# Ethernet_HPS_Interface.net
KiCad netlist of a schematic drawn in Altium Designer
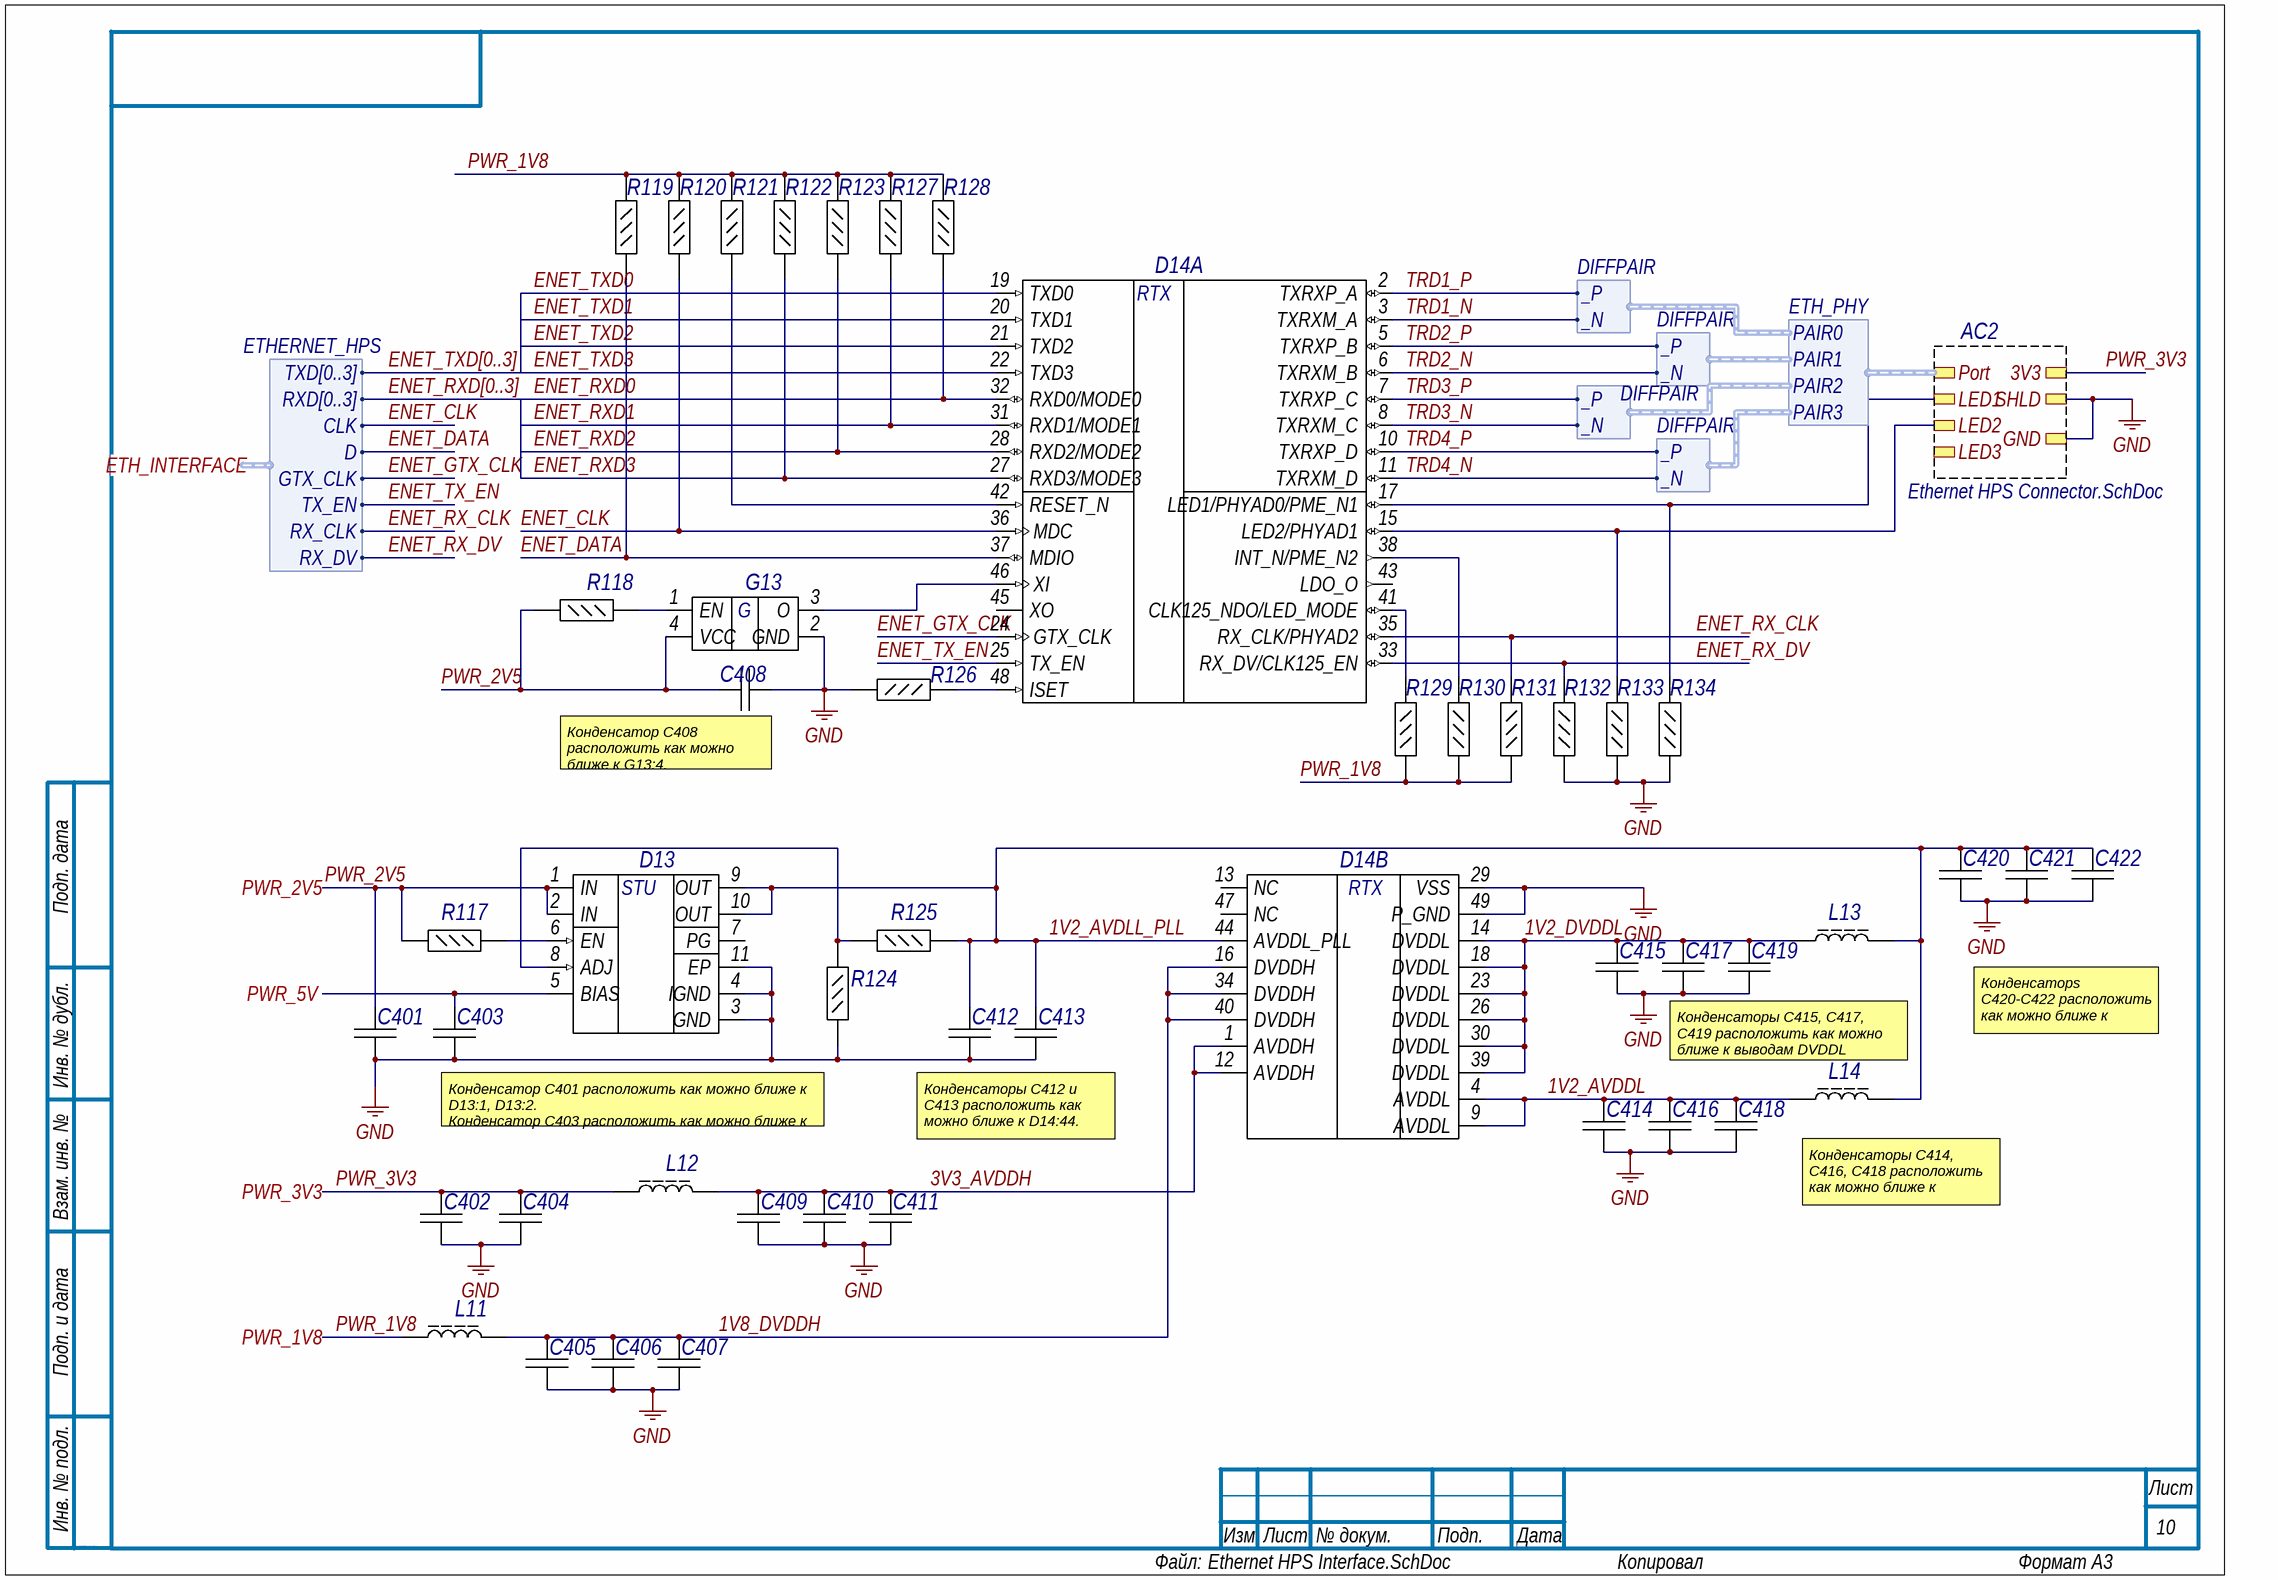
[diagram p0: Ethernet HPS Interface.SchDoc]

(export (version "E")
  (design (tool "Eeschema 10.0.6"))
  (components
    (comp (ref "C401")
      (value "C2012X5R1C106K085AC")
      (footprint "CAPC2013X100X20NL20")
      (description "Chip Capacitor, 10 uF, +/- 10%, 16 V, -55 to 85 degC, 0805 (2012 Metric), RoHS, Tape and Reel")
      (fields (field (name "TOLERANCE") "10%"))
      (libsource (lib "MiniPC DB") (part "CAP_NP"))
    )
    (comp (ref "C402")
      (value "C2012X5R1C106K085AC")
      (footprint "CAPC2013X100X20NL20")
      (description "Chip Capacitor, 10 uF, +/- 10%, 16 V, -55 to 85 degC, 0805 (2012 Metric), RoHS, Tape and Reel")
      (fields (field (name "TOLERANCE") "10%"))
      (libsource (lib "MiniPC DB") (part "CAP_NP"))
    )
    (comp (ref "C403")
      (value "CGB2A1X5R1E105K033BC")
      (footprint "CAPC1005X33X10LL5")
      (description "Chip Capacitor, 1 uF, +/- 10%, 25 V, -55 to 85 degC, 0402 (1005 Metric), RoHS, Tape and Reel")
      (fields (field (name "TOLERANCE") "10%"))
      (libsource (lib "MiniPC DB") (part "CAP_NP"))
    )
    (comp (ref "C404")
      (value "C2012X5R1C106K085AC")
      (footprint "CAPC2013X100X20NL20")
      (description "Chip Capacitor, 10 uF, +/- 10%, 16 V, -55 to 85 degC, 0805 (2012 Metric), RoHS, Tape and Reel")
      (fields (field (name "TOLERANCE") "10%"))
      (libsource (lib "MiniPC DB") (part "CAP_NP"))
    )
    (comp (ref "C405")
      (value "GRM31CR61E226KE15L")
      (footprint "CAPC3216X180X55ML20T25")
      (description "Chip Capacitor, 22 uF, +/- 10%, 25 V, -55 to 85 degC, 1206 (3216 Metric), RoHS, Tape and Reel")
      (fields (field (name "TOLERANCE") "10%"))
      (libsource (lib "MiniPC DB") (part "CAP_NP"))
    )
    (comp (ref "C406")
      (value "GRM188R61A225KE34x")
      (footprint "CAPC1608X90X35ML10T15")
      (description "Chip Capacitor, 2.2 uF, +/- 10%, 10 V, -55 to 85 degC, 0603 (1608 Metric), RoHS, Tape and Reel")
      (fields (field (name "TOLERANCE") "10%"))
      (libsource (lib "MiniPC DB") (part "CAP_NP"))
    )
    (comp (ref "C407")
      (value "C1005X7R1E104M")
      (footprint "CAPC1005X55X10LL05")
      (description "Chip Capacitor, 0.1 uF, +/- 20%, 25 V, -55 to 125 degC, 0402 (1005 Metric), RoHS, Tape and Reel")
      (fields (field (name "TOLERANCE") "20%"))
      (libsource (lib "MiniPC DB") (part "CAP_NP"))
    )
    (comp (ref "C408")
      (value "GRM155R71H103KA88D")
      (footprint "CAPC1005X55X25ML05T10")
      (description "Chip Capacitor, 10 nF, +/- 10%, 50 V, -55 to 125 degC, 0402 (1005 Metric), RoHS, Tape and Reel")
      (fields (field (name "TOLERANCE") "10%") (field (name "MANUFACTURER") "Basic Passives"))
      (libsource (lib "MiniPC DB") (part "CAP_NP"))
    )
    (comp (ref "C409")
      (value "GRM31CR61E226KE15L")
      (footprint "CAPC3216X180X55ML20T25")
      (description "Chip Capacitor, 22 uF, +/- 10%, 25 V, -55 to 85 degC, 1206 (3216 Metric), RoHS, Tape and Reel")
      (fields (field (name "TOLERANCE") "10%"))
      (libsource (lib "MiniPC DB") (part "CAP_NP"))
    )
    (comp (ref "C410")
      (value "GRM188R61A225KE34x")
      (footprint "CAPC1608X90X35ML10T15")
      (description "Chip Capacitor, 2.2 uF, +/- 10%, 10 V, -55 to 85 degC, 0603 (1608 Metric), RoHS, Tape and Reel")
      (fields (field (name "TOLERANCE") "10%"))
      (libsource (lib "MiniPC DB") (part "CAP_NP"))
    )
    (comp (ref "C411")
      (value "C1005X7R1E104M")
      (footprint "CAPC1005X55X10LL05")
      (description "Chip Capacitor, 0.1 uF, +/- 20%, 25 V, -55 to 125 degC, 0402 (1005 Metric), RoHS, Tape and Reel")
      (fields (field (name "TOLERANCE") "20%"))
      (libsource (lib "MiniPC DB") (part "CAP_NP"))
    )
    (comp (ref "C412")
      (value "GRM31CR61E226KE15L")
      (footprint "CAPC3216X180X55ML20T25")
      (description "Chip Capacitor, 22 uF, +/- 10%, 25 V, -55 to 85 degC, 1206 (3216 Metric), RoHS, Tape and Reel")
      (fields (field (name "TOLERANCE") "10%"))
      (libsource (lib "MiniPC DB") (part "CAP_NP"))
    )
    (comp (ref "C413")
      (value "GRM188R61A225KE34x")
      (footprint "CAPC1608X90X35ML10T15")
      (description "Chip Capacitor, 2.2 uF, +/- 10%, 10 V, -55 to 85 degC, 0603 (1608 Metric), RoHS, Tape and Reel")
      (fields (field (name "TOLERANCE") "10%"))
      (libsource (lib "MiniPC DB") (part "CAP_NP"))
    )
    (comp (ref "C414")
      (value "C1005X7R1E104M")
      (footprint "CAPC1005X55X10LL05")
      (description "Chip Capacitor, 0.1 uF, +/- 20%, 25 V, -55 to 125 degC, 0402 (1005 Metric), RoHS, Tape and Reel")
      (fields (field (name "TOLERANCE") "20%"))
      (libsource (lib "MiniPC DB") (part "CAP_NP"))
    )
    (comp (ref "C415")
      (value "C1005X7R1E104M")
      (footprint "CAPC1005X55X10LL05")
      (description "Chip Capacitor, 0.1 uF, +/- 20%, 25 V, -55 to 125 degC, 0402 (1005 Metric), RoHS, Tape and Reel")
      (fields (field (name "TOLERANCE") "20%"))
      (libsource (lib "MiniPC DB") (part "CAP_NP"))
    )
    (comp (ref "C416")
      (value "GRM188R61A225KE34x")
      (footprint "CAPC1608X90X35ML10T15")
      (description "Chip Capacitor, 2.2 uF, +/- 10%, 10 V, -55 to 85 degC, 0603 (1608 Metric), RoHS, Tape and Reel")
      (fields (field (name "TOLERANCE") "10%"))
      (libsource (lib "MiniPC DB") (part "CAP_NP"))
    )
    (comp (ref "C417")
      (value "GRM188R61A225KE34x")
      (footprint "CAPC1608X90X35ML10T15")
      (description "Chip Capacitor, 2.2 uF, +/- 10%, 10 V, -55 to 85 degC, 0603 (1608 Metric), RoHS, Tape and Reel")
      (fields (field (name "TOLERANCE") "10%"))
      (libsource (lib "MiniPC DB") (part "CAP_NP"))
    )
    (comp (ref "C418")
      (value "GRM31CR61E226KE15L")
      (footprint "CAPC3216X180X55ML20T25")
      (description "Chip Capacitor, 22 uF, +/- 10%, 25 V, -55 to 85 degC, 1206 (3216 Metric), RoHS, Tape and Reel")
      (fields (field (name "TOLERANCE") "10%"))
      (libsource (lib "MiniPC DB") (part "CAP_NP"))
    )
    (comp (ref "C419")
      (value "GRM31CR61E226KE15L")
      (footprint "CAPC3216X180X55ML20T25")
      (description "Chip Capacitor, 22 uF, +/- 10%, 25 V, -55 to 85 degC, 1206 (3216 Metric), RoHS, Tape and Reel")
      (fields (field (name "TOLERANCE") "10%"))
      (libsource (lib "MiniPC DB") (part "CAP_NP"))
    )
    (comp (ref "C420")
      (value "C1005X7R1E104M")
      (footprint "CAPC1005X55X10LL05")
      (description "Chip Capacitor, 0.1 uF, +/- 20%, 25 V, -55 to 125 degC, 0402 (1005 Metric), RoHS, Tape and Reel")
      (fields (field (name "TOLERANCE") "20%"))
      (libsource (lib "MiniPC DB") (part "CAP_NP"))
    )
    (comp (ref "C421")
      (value "GRM188R61A225KE34x")
      (footprint "CAPC1608X90X35ML10T15")
      (description "Chip Capacitor, 2.2 uF, +/- 10%, 10 V, -55 to 85 degC, 0603 (1608 Metric), RoHS, Tape and Reel")
      (fields (field (name "TOLERANCE") "10%"))
      (libsource (lib "MiniPC DB") (part "CAP_NP"))
    )
    (comp (ref "C422")
      (value "GRM31CR61E226KE15L")
      (footprint "CAPC3216X180X55ML20T25")
      (description "Chip Capacitor, 22 uF, +/- 10%, 25 V, -55 to 85 degC, 1206 (3216 Metric), RoHS, Tape and Reel")
      (fields (field (name "TOLERANCE") "10%"))
      (libsource (lib "MiniPC DB") (part "CAP_NP"))
    )
    (comp (ref "D13")
      (value "LTC3026EDD-1#PBF")
      (footprint "LT-DD-10_V")
      (fields (field (name "MANUFACTURER") "Linear Technology"))
      (libsource (lib "MiniPC DB") (part "LTC3026"))
    )
    (comp (ref "D14")
      (value "KSZ9031RNXCA")
      (footprint "MICL-QFN-48_V")
      (description "Gigabit Ethernet Transceiver with RGMII Support, 1.14 to 1.26 V, 0 to 70 degC, 48-Pin QFN, RoHS")
      (fields (field (name "MANUFACTURER") "Micrel"))
      (libsource (lib "MiniPC DB") (part "KSZ9031RNX"))
    )
    (comp (ref "G13")
      (value "SG-310SDF 25.0000M-B3")
      (footprint "EPSON-SG-310-4_V")
      (description "Crystal Oscillator (SPXO), 2.5 V, 25 MHz, -20 to 70 degC, 4-Pin SMD, RoHS, Tape and Reel")
      (libsource (lib "MiniPC DB") (part "GEN"))
    )
    (comp (ref "L11")
      (value "742792609")
      (footprint "SMD-0603")
      (description "SMD EMI Suppression Ferrite Bead WE-CBF, Z = 30 Ohm")
      (libsource (lib "MiniPC DB") (part "Choke"))
    )
    (comp (ref "L12")
      (value "742792609")
      (footprint "SMD-0603")
      (description "SMD EMI Suppression Ferrite Bead WE-CBF, Z = 30 Ohm")
      (libsource (lib "MiniPC DB") (part "Choke"))
    )
    (comp (ref "L13")
      (value "742792609")
      (footprint "SMD-0603")
      (description "SMD EMI Suppression Ferrite Bead WE-CBF, Z = 30 Ohm")
      (libsource (lib "") (part "Choke_1"))
    )
    (comp (ref "L14")
      (value "742792609")
      (footprint "SMD-0603")
      (description "SMD EMI Suppression Ferrite Bead WE-CBF, Z = 30 Ohm")
      (libsource (lib "") (part "Choke_1"))
    )
    (comp (ref "R117")
      (value "ERJ-2RKF1002X")
      (footprint "RESC1005X40X25LL05T05")
      (description "Chip Resistor, 10 KOhm, +/- 1%, 100 mW, -55 to 155 degC, 0402 (1005 Metric), RoHS, Tape and Reel")
      (fields (field (name "TOLERANCE") "1%") (field (name "MANUFACTURER") "Basic Passives"))
      (libsource (lib "") (part "RES-0.05_2"))
    )
    (comp (ref "R118")
      (value "ERJ-2RKF1002X")
      (footprint "RESC1005X40X25LL05T05")
      (description "Chip Resistor, 10 KOhm, +/- 1%, 100 mW, -55 to 155 degC, 0402 (1005 Metric), RoHS, Tape and Reel")
      (fields (field (name "TOLERANCE") "1%") (field (name "MANUFACTURER") "Basic Passives"))
      (libsource (lib "") (part "RES-0.05_2"))
    )
    (comp (ref "R119")
      (value "NRC04F49R9TRF")
      (footprint "RESC1005X35X25NL8T10")
      (description "Chip Resistor, 49.9 Ohm, +/- 1%, 0.06 W, -55 to 155 degC, 0402 (1005 Metric), RoHS, Tape and Reel")
      (fields (field (name "TOLERANCE") "1%"))
      (libsource (lib "") (part "RES-0.05_1"))
    )
    (comp (ref "R120")
      (value "ERJ-2RKF4701X")
      (footprint "RESC1005X40X25LL05T05")
      (description "Chip Resistor, 4.7 KOhm, +/- 1%, 0.1 W, -55 to 155 degC, 0402 (1005 Metric), RoHS, Tape and Reel")
      (fields (field (name "TOLERANCE") "1%"))
      (libsource (lib "") (part "RES-0.05_1"))
    )
    (comp (ref "R121")
      (value "NRC04F49R9TRF")
      (footprint "RESC1005X35X25NL8T10")
      (description "Chip Resistor, 49.9 Ohm, +/- 1%, 0.06 W, -55 to 155 degC, 0402 (1005 Metric), RoHS, Tape and Reel")
      (fields (field (name "TOLERANCE") "1%"))
      (libsource (lib "") (part "RES-0.05_1"))
    )
    (comp (ref "R122")
      (value "ERJ-2RKF4701X")
      (footprint "RESC1005X40X25LL05T05")
      (description "Chip Resistor, 4.7 KOhm, +/- 1%, 0.1 W, -55 to 155 degC, 0402 (1005 Metric), RoHS, Tape and Reel")
      (fields (field (name "TOLERANCE") "1%"))
      (libsource (lib "MiniPC DB") (part "RES-0.05"))
    )
    (comp (ref "R123")
      (value "ERJ-2RKF4701X")
      (footprint "RESC1005X40X25LL05T05")
      (description "Chip Resistor, 4.7 KOhm, +/- 1%, 0.1 W, -55 to 155 degC, 0402 (1005 Metric), RoHS, Tape and Reel")
      (fields (field (name "TOLERANCE") "1%"))
      (libsource (lib "MiniPC DB") (part "RES-0.05"))
    )
    (comp (ref "R124")
      (value "ERJ-2RKF1001X")
      (footprint "RESC1005X40X25LL05T05")
      (description "Chip Resistor, 1 KOhm, +/- 1%, 100 mW, -55 to 155 degC, 0402 (1005 Metric), RoHS, Tape and Reel")
      (fields (field (name "TOLERANCE") "1%") (field (name "MANUFACTURER") "Basic Passives"))
      (libsource (lib "") (part "RES-0.05_1"))
    )
    (comp (ref "R125")
      (value "ERJ-2RKF2001X")
      (footprint "RESC1005X40X25LL05T05")
      (description "Chip Resistor, 2 KOhm, +/- 1%, 100 mW, -55 to 155 degC, 0402 (1005 Metric), RoHS, Tape and Reel")
      (fields (field (name "TOLERANCE") "1%") (field (name "MANUFACTURER") "Basic Passives"))
      (libsource (lib "") (part "RES-0.05_2"))
    )
    (comp (ref "R126")
      (value "CRCW040212K1FKED")
      (footprint "RESC1005X40X25LL05T05")
      (description "Chip Resistor, 12.1 KOhm, +/- 1%, 63 mW, -55 to 155 degC, 0402 (1005 Metric), RoHS, Tape and Reel")
      (fields (field (name "TOLERANCE") "1%") (field (name "MANUFACTURER") "Basic Passives"))
      (libsource (lib "") (part "RES-0.05_3"))
    )
    (comp (ref "R127")
      (value "ERJ-2RKF4701X")
      (footprint "RESC1005X40X25LL05T05")
      (description "Chip Resistor, 4.7 KOhm, +/- 1%, 0.1 W, -55 to 155 degC, 0402 (1005 Metric), RoHS, Tape and Reel")
      (fields (field (name "TOLERANCE") "1%"))
      (libsource (lib "MiniPC DB") (part "RES-0.05"))
    )
    (comp (ref "R128")
      (value "ERJ-2RKF4701X")
      (footprint "RESC1005X40X25LL05T05")
      (description "Chip Resistor, 4.7 KOhm, +/- 1%, 0.1 W, -55 to 155 degC, 0402 (1005 Metric), RoHS, Tape and Reel")
      (fields (field (name "TOLERANCE") "1%"))
      (libsource (lib "MiniPC DB") (part "RES-0.05"))
    )
    (comp (ref "R129")
      (value "ERJ-2RKF4701X")
      (footprint "RESC1005X40X25LL05T05")
      (description "Chip Resistor, 4.7 KOhm, +/- 1%, 0.1 W, -55 to 155 degC, 0402 (1005 Metric), RoHS, Tape and Reel")
      (fields (field (name "TOLERANCE") "1%"))
      (libsource (lib "") (part "RES-0.05_1"))
    )
    (comp (ref "R130")
      (value "ERJ-2RKF4701X")
      (footprint "RESC1005X40X25LL05T05")
      (description "Chip Resistor, 4.7 KOhm, +/- 1%, 0.1 W, -55 to 155 degC, 0402 (1005 Metric), RoHS, Tape and Reel")
      (fields (field (name "TOLERANCE") "1%"))
      (libsource (lib "MiniPC DB") (part "RES-0.05"))
    )
    (comp (ref "R131")
      (value "ERJ-2RKF4701X")
      (footprint "RESC1005X40X25LL05T05")
      (description "Chip Resistor, 4.7 KOhm, +/- 1%, 0.1 W, -55 to 155 degC, 0402 (1005 Metric), RoHS, Tape and Reel")
      (fields (field (name "TOLERANCE") "1%"))
      (libsource (lib "") (part "RES-0.05_1"))
    )
    (comp (ref "R132")
      (value "ERJ-2RKF4701X")
      (footprint "RESC1005X40X25LL05T05")
      (description "Chip Resistor, 4.7 KOhm, +/- 1%, 0.1 W, -55 to 155 degC, 0402 (1005 Metric), RoHS, Tape and Reel")
      (fields (field (name "TOLERANCE") "1%"))
      (libsource (lib "MiniPC DB") (part "RES-0.05"))
    )
    (comp (ref "R133")
      (value "ERJ-2RKF4701X")
      (footprint "RESC1005X40X25LL05T05")
      (description "Chip Resistor, 4.7 KOhm, +/- 1%, 0.1 W, -55 to 155 degC, 0402 (1005 Metric), RoHS, Tape and Reel")
      (fields (field (name "TOLERANCE") "1%"))
      (libsource (lib "MiniPC DB") (part "RES-0.05"))
    )
    (comp (ref "R134")
      (value "ERJ-2RKF4701X")
      (footprint "RESC1005X40X25LL05T05")
      (description "Chip Resistor, 4.7 KOhm, +/- 1%, 0.1 W, -55 to 155 degC, 0402 (1005 Metric), RoHS, Tape and Reel")
      (fields (field (name "TOLERANCE") "1%"))
      (libsource (lib "MiniPC DB") (part "RES-0.05"))
    )
  )
  (nets
    (net (code "4") (name "/1V2_AVDDL") (class "Default")
      (node (ref "C414") (pin "2") (pinfunction "2_2") (pintype "passive"))
      (node (ref "C416") (pin "2") (pinfunction "2_2") (pintype "passive"))
      (node (ref "C418") (pin "2") (pinfunction "2_2") (pintype "passive"))
      (node (ref "D14") (pin "4") (pinfunction "AVDDL_4") (pintype "power_in"))
      (node (ref "D14") (pin "9") (pinfunction "AVDDL_9") (pintype "power_in"))
      (node (ref "L14") (pin "2") (pinfunction "2_2") (pintype "passive"))
    )
    (net (code "5") (name "/1V2_AVDLL_PLL") (class "Default")
      (node (ref "C412") (pin "2") (pinfunction "2_2") (pintype "passive"))
      (node (ref "C413") (pin "2") (pinfunction "2_2") (pintype "passive"))
      (node (ref "C420") (pin "2") (pinfunction "2_2") (pintype "passive"))
      (node (ref "C421") (pin "2") (pinfunction "2_2") (pintype "passive"))
      (node (ref "C422") (pin "2") (pinfunction "2_2") (pintype "passive"))
      (node (ref "D13") (pin "10") (pinfunction "OUT_10") (pintype "power_in"))
      (node (ref "D13") (pin "9") (pinfunction "OUT_9") (pintype "power_in"))
      (node (ref "D14") (pin "44") (pinfunction "AVDDL_PLL_44") (pintype "power_in"))
      (node (ref "L13") (pin "1") (pinfunction "1_1") (pintype "passive"))
      (node (ref "L14") (pin "1") (pinfunction "1_1") (pintype "passive"))
      (node (ref "R125") (pin "2") (pinfunction "2_2") (pintype "passive"))
    )
    (net (code "6") (name "/1V2_DVDDL") (class "Default")
      (node (ref "C415") (pin "2") (pinfunction "2_2") (pintype "passive"))
      (node (ref "C417") (pin "2") (pinfunction "2_2") (pintype "passive"))
      (node (ref "C419") (pin "2") (pinfunction "2_2") (pintype "passive"))
      (node (ref "D14") (pin "14") (pinfunction "DVDDL_14") (pintype "power_in"))
      (node (ref "D14") (pin "18") (pinfunction "DVDDL_18") (pintype "power_in"))
      (node (ref "D14") (pin "23") (pinfunction "DVDDL_23") (pintype "power_in"))
      (node (ref "D14") (pin "26") (pinfunction "DVDDL_26") (pintype "power_in"))
      (node (ref "D14") (pin "30") (pinfunction "DVDDL_30") (pintype "power_in"))
      (node (ref "D14") (pin "39") (pinfunction "DVDDL_39") (pintype "power_in"))
      (node (ref "L13") (pin "2") (pinfunction "2_2") (pintype "passive"))
    )
    (net (code "7") (name "/1V8_DVDDH") (class "Default")
      (node (ref "C405") (pin "2") (pinfunction "2_2") (pintype "passive"))
      (node (ref "C406") (pin "2") (pinfunction "2_2") (pintype "passive"))
      (node (ref "C407") (pin "1") (pinfunction "1_1") (pintype "passive"))
      (node (ref "D14") (pin "16") (pinfunction "DVDDH_16") (pintype "power_in"))
      (node (ref "D14") (pin "34") (pinfunction "DVDDH_34") (pintype "power_in"))
      (node (ref "D14") (pin "40") (pinfunction "DVDDH_40") (pintype "power_in"))
      (node (ref "L11") (pin "2") (pinfunction "2_2") (pintype "passive"))
    )
    (net (code "8") (name "/3V3_AVDDH") (class "Default")
      (node (ref "C409") (pin "2") (pinfunction "2_2") (pintype "passive"))
      (node (ref "C410") (pin "2") (pinfunction "2_2") (pintype "passive"))
      (node (ref "C411") (pin "2") (pinfunction "2_2") (pintype "passive"))
      (node (ref "D14") (pin "1") (pinfunction "AVDDH_1") (pintype "power_in"))
      (node (ref "D14") (pin "12") (pinfunction "AVDDH_12") (pintype "power_in"))
      (node (ref "L12") (pin "2") (pinfunction "2_2") (pintype "passive"))
    )
    (net (code "9") (name "/ENET_CLK") (class "Default")
      (node (ref "D14") (pin "36") (pinfunction "MDC_36") (pintype "input"))
      (node (ref "R120") (pin "1") (pinfunction "1_1") (pintype "passive"))
    )
    (net (code "10") (name "/ENET_DATA") (class "Default")
      (node (ref "D14") (pin "37") (pinfunction "MDIO_37") (pintype "bidirectional"))
      (node (ref "R119") (pin "1") (pinfunction "1_1") (pintype "passive"))
    )
    (net (code "11") (name "/ENET_GTX_CLK") (class "Default")
      (node (ref "D14") (pin "24") (pinfunction "GTX_CLK_24") (pintype "input"))
    )
    (net (code "12") (name "/ENET_RXD0") (class "Default")
      (node (ref "D14") (pin "32") (pinfunction "RXD0/MODE0_32") (pintype "bidirectional"))
      (node (ref "R128") (pin "2") (pinfunction "2_2") (pintype "passive"))
    )
    (net (code "13") (name "/ENET_RXD1") (class "Default")
      (node (ref "D14") (pin "31") (pinfunction "RXD1/MODE1_31") (pintype "bidirectional"))
      (node (ref "R127") (pin "2") (pinfunction "2_2") (pintype "passive"))
    )
    (net (code "14") (name "/ENET_RXD2") (class "Default")
      (node (ref "D14") (pin "28") (pinfunction "RXD2/MODE2_28") (pintype "bidirectional"))
      (node (ref "R123") (pin "2") (pinfunction "2_2") (pintype "passive"))
    )
    (net (code "15") (name "/ENET_RXD3") (class "Default")
      (node (ref "D14") (pin "27") (pinfunction "RXD3/MODE3_27") (pintype "bidirectional"))
      (node (ref "R122") (pin "2") (pinfunction "2_2") (pintype "passive"))
    )
    (net (code "17") (name "/ENET_RX_CLK") (class "Default")
      (node (ref "D14") (pin "35") (pinfunction "RX_CLK/PHYAD2_35") (pintype "bidirectional"))
      (node (ref "R131") (pin "2") (pinfunction "2_2") (pintype "passive"))
    )
    (net (code "18") (name "/ENET_RX_DV") (class "Default")
      (node (ref "D14") (pin "33") (pinfunction "RX_DV/CLK125_EN_33") (pintype "bidirectional"))
      (node (ref "R132") (pin "1") (pinfunction "1_1") (pintype "passive"))
    )
    (net (code "19") (name "/ENET_TXD0") (class "Default")
      (node (ref "D14") (pin "19") (pinfunction "TXD0_19") (pintype "input"))
    )
    (net (code "20") (name "/ENET_TXD1") (class "Default")
      (node (ref "D14") (pin "20") (pinfunction "TXD1_20") (pintype "input"))
    )
    (net (code "21") (name "/ENET_TXD2") (class "Default")
      (node (ref "D14") (pin "21") (pinfunction "TXD2_21") (pintype "input"))
    )
    (net (code "22") (name "/ENET_TXD3") (class "Default")
      (node (ref "D14") (pin "22") (pinfunction "TXD3_22") (pintype "input"))
    )
    (net (code "24") (name "/ENET_TX_EN") (class "Default")
      (node (ref "D14") (pin "25") (pinfunction "TX_EN_25") (pintype "input"))
    )
    (net (code "25") (name "/LED1") (class "Default")
      (node (ref "D14") (pin "17") (pinfunction "LED1/PHYAD0/PME_N1_17") (pintype "bidirectional"))
      (node (ref "R134") (pin "1") (pinfunction "1_1") (pintype "passive"))
    )
    (net (code "26") (name "/LED2") (class "Default")
      (node (ref "D14") (pin "15") (pinfunction "LED2/PHYAD1_15") (pintype "bidirectional"))
      (node (ref "R133") (pin "1") (pinfunction "1_1") (pintype "passive"))
    )
    (net (code "28") (name "/PWR_1V8") (class "Default")
      (node (ref "L11") (pin "1") (pinfunction "1_1") (pintype "passive"))
      (node (ref "R119") (pin "2") (pinfunction "2_2") (pintype "passive"))
      (node (ref "R120") (pin "2") (pinfunction "2_2") (pintype "passive"))
      (node (ref "R121") (pin "2") (pinfunction "2_2") (pintype "passive"))
      (node (ref "R122") (pin "1") (pinfunction "1_1") (pintype "passive"))
      (node (ref "R123") (pin "1") (pinfunction "1_1") (pintype "passive"))
      (node (ref "R127") (pin "1") (pinfunction "1_1") (pintype "passive"))
      (node (ref "R128") (pin "1") (pinfunction "1_1") (pintype "passive"))
      (node (ref "R129") (pin "1") (pinfunction "1_1") (pintype "passive"))
      (node (ref "R130") (pin "2") (pinfunction "2_2") (pintype "passive"))
      (node (ref "R131") (pin "1") (pinfunction "1_1") (pintype "passive"))
    )
    (net (code "29") (name "/PWR_2V5") (class "Default")
      (node (ref "C401") (pin "2") (pinfunction "2_2") (pintype "passive"))
      (node (ref "C408") (pin "2") (pinfunction "2_2") (pintype "passive"))
      (node (ref "D13") (pin "1") (pinfunction "IN_1") (pintype "power_in"))
      (node (ref "D13") (pin "2") (pinfunction "IN_2") (pintype "power_in"))
      (node (ref "G13") (pin "4") (pinfunction "VCC_4") (pintype "passive"))
      (node (ref "R117") (pin "1") (pinfunction "1_1") (pintype "passive"))
      (node (ref "R118") (pin "1") (pinfunction "1_1") (pintype "passive"))
    )
    (net (code "30") (name "/PWR_3V3") (class "Default")
      (node (ref "C402") (pin "2") (pinfunction "2_2") (pintype "passive"))
      (node (ref "C404") (pin "2") (pinfunction "2_2") (pintype "passive"))
      (node (ref "L12") (pin "1") (pinfunction "1_1") (pintype "passive"))
    )
    (net (code "31") (name "/PWR_5V") (class "Default")
      (node (ref "C403") (pin "2") (pinfunction "2_2") (pintype "passive"))
      (node (ref "D13") (pin "5") (pinfunction "BIAS_5") (pintype "power_in"))
    )
    (net (code "32") (name "/TRD1_N") (class "Default")
      (node (ref "D14") (pin "3") (pinfunction "TXRXM_A_3") (pintype "bidirectional"))
    )
    (net (code "33") (name "/TRD1_P") (class "Default")
      (node (ref "D14") (pin "2") (pinfunction "TXRXP_A_2") (pintype "bidirectional"))
    )
    (net (code "34") (name "/TRD2_N") (class "Default")
      (node (ref "D14") (pin "6") (pinfunction "TXRXM_B_6") (pintype "bidirectional"))
    )
    (net (code "35") (name "/TRD2_P") (class "Default")
      (node (ref "D14") (pin "5") (pinfunction "TXRXP_B_5") (pintype "bidirectional"))
    )
    (net (code "36") (name "/TRD3_N") (class "Default")
      (node (ref "D14") (pin "8") (pinfunction "TXRXM_C_8") (pintype "bidirectional"))
    )
    (net (code "37") (name "/TRD3_P") (class "Default")
      (node (ref "D14") (pin "7") (pinfunction "TXRXP_C_7") (pintype "bidirectional"))
    )
    (net (code "38") (name "/TRD4_N") (class "Default")
      (node (ref "D14") (pin "11") (pinfunction "TXRXM_D_11") (pintype "bidirectional"))
    )
    (net (code "39") (name "/TRD4_P") (class "Default")
      (node (ref "D14") (pin "10") (pinfunction "TXRXP_D_10") (pintype "bidirectional"))
    )
    (net (code "43") (name "GND") (class "Default")
      (node (ref "C401") (pin "1") (pinfunction "1_1") (pintype "passive"))
      (node (ref "C402") (pin "1") (pinfunction "1_1") (pintype "passive"))
      (node (ref "C403") (pin "1") (pinfunction "1_1") (pintype "passive"))
      (node (ref "C404") (pin "1") (pinfunction "1_1") (pintype "passive"))
      (node (ref "C405") (pin "1") (pinfunction "1_1") (pintype "passive"))
      (node (ref "C406") (pin "1") (pinfunction "1_1") (pintype "passive"))
      (node (ref "C407") (pin "2") (pinfunction "2_2") (pintype "passive"))
      (node (ref "C408") (pin "1") (pinfunction "1_1") (pintype "passive"))
      (node (ref "C409") (pin "1") (pinfunction "1_1") (pintype "passive"))
      (node (ref "C410") (pin "1") (pinfunction "1_1") (pintype "passive"))
      (node (ref "C411") (pin "1") (pinfunction "1_1") (pintype "passive"))
      (node (ref "C412") (pin "1") (pinfunction "1_1") (pintype "passive"))
      (node (ref "C413") (pin "1") (pinfunction "1_1") (pintype "passive"))
      (node (ref "C414") (pin "1") (pinfunction "1_1") (pintype "passive"))
      (node (ref "C415") (pin "1") (pinfunction "1_1") (pintype "passive"))
      (node (ref "C416") (pin "1") (pinfunction "1_1") (pintype "passive"))
      (node (ref "C417") (pin "1") (pinfunction "1_1") (pintype "passive"))
      (node (ref "C418") (pin "1") (pinfunction "1_1") (pintype "passive"))
      (node (ref "C419") (pin "1") (pinfunction "1_1") (pintype "passive"))
      (node (ref "C420") (pin "1") (pinfunction "1_1") (pintype "passive"))
      (node (ref "C421") (pin "1") (pinfunction "1_1") (pintype "passive"))
      (node (ref "C422") (pin "1") (pinfunction "1_1") (pintype "passive"))
      (node (ref "D13") (pin "11") (pinfunction "EP_11") (pintype "passive"))
      (node (ref "D13") (pin "3") (pinfunction "GND_3") (pintype "power_in"))
      (node (ref "D13") (pin "4") (pinfunction "IGND_4") (pintype "power_in"))
      (node (ref "D14") (pin "29") (pinfunction "VSS_29") (pintype "power_in"))
      (node (ref "D14") (pin "49") (pinfunction "P_GND_49") (pintype "power_in"))
      (node (ref "G13") (pin "2") (pinfunction "GND_2") (pintype "passive"))
      (node (ref "R124") (pin "1") (pinfunction "1_1") (pintype "passive"))
      (node (ref "R126") (pin "2") (pinfunction "2_2") (pintype "passive"))
      (node (ref "R132") (pin "2") (pinfunction "2_2") (pintype "passive"))
      (node (ref "R133") (pin "2") (pinfunction "2_2") (pintype "passive"))
      (node (ref "R134") (pin "2") (pinfunction "2_2") (pintype "passive"))
    )
    (net (code "44") (name "Net-(D13-ADJ)") (class "Default")
      (node (ref "D13") (pin "8") (pinfunction "ADJ_8") (pintype "input"))
      (node (ref "R124") (pin "2") (pinfunction "2_2") (pintype "passive"))
      (node (ref "R125") (pin "1") (pinfunction "1_1") (pintype "passive"))
    )
    (net (code "45") (name "Net-(D13-EN)") (class "Default")
      (node (ref "D13") (pin "6") (pinfunction "EN_6") (pintype "input"))
      (node (ref "R117") (pin "2") (pinfunction "2_2") (pintype "passive"))
    )
    (net (code "46") (name "Net-(D14A-CLK125_NDO{slash}LED_MODE)") (class "Default")
      (node (ref "D14") (pin "41") (pinfunction "CLK125_NDO/LED_MODE_41") (pintype "bidirectional"))
      (node (ref "R129") (pin "2") (pinfunction "2_2") (pintype "passive"))
    )
    (net (code "47") (name "Net-(D14A-INT_N{slash}PME_N2)") (class "Default")
      (node (ref "D14") (pin "38") (pinfunction "INT_N/PME_N2_38") (pintype "output"))
      (node (ref "R130") (pin "1") (pinfunction "1_1") (pintype "passive"))
    )
    (net (code "48") (name "Net-(D14A-ISET)") (class "Default")
      (node (ref "D14") (pin "48") (pinfunction "ISET_48") (pintype "input"))
      (node (ref "R126") (pin "1") (pinfunction "1_1") (pintype "passive"))
    )
    (net (code "49") (name "Net-(D14A-RESET_N)") (class "Default")
      (node (ref "D14") (pin "42") (pinfunction "RESET_N_42") (pintype "input"))
      (node (ref "R121") (pin "1") (pinfunction "1_1") (pintype "passive"))
    )
    (net (code "50") (name "Net-(D14A-XI)") (class "Default")
      (node (ref "D14") (pin "46") (pinfunction "XI_46") (pintype "input"))
      (node (ref "G13") (pin "3") (pinfunction "O_3") (pintype "passive"))
    )
    (net (code "51") (name "Net-(G13-EN)") (class "Default")
      (node (ref "G13") (pin "1") (pinfunction "EN_1") (pintype "passive"))
      (node (ref "R118") (pin "2") (pinfunction "2_2") (pintype "passive"))
    )
    (net (code "52") (name "unconnected-(D13-PG-Pad7)") (class "Default")
      (node (ref "D13") (pin "7") (pinfunction "PG_7") (pintype "tri_state"))
    )
    (net (code "53") (name "unconnected-(D14A-LDO_O-Pad43)") (class "Default")
      (node (ref "D14") (pin "43") (pinfunction "LDO_O_43") (pintype "output"))
    )
    (net (code "54") (name "unconnected-(D14A-XO-Pad45)") (class "Default")
      (node (ref "D14") (pin "45") (pinfunction "XO_45") (pintype "passive"))
    )
    (net (code "55") (name "unconnected-(D14B-NC-Pad13)") (class "Default")
      (node (ref "D14") (pin "13") (pinfunction "NC_13") (pintype "passive"))
    )
    (net (code "56") (name "unconnected-(D14B-NC-Pad47)") (class "Default")
      (node (ref "D14") (pin "47") (pinfunction "NC_47") (pintype "passive"))
    )
  )
)
